# FaultRelay.net
KiCad netlist of a schematic drawn in Altium Designer
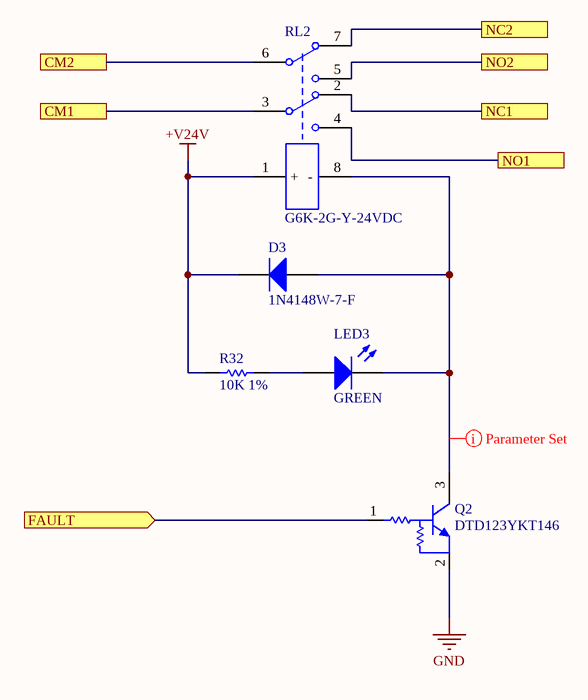
[diagram p0: FaultRelay.SchDoc]

(export (version "E")
  (design (tool "Eeschema 10.0.6"))
  (components
    (comp (ref "D3")
      (value "1N4148W-7-F")
      (footprint "MC1:DIOD-SOD123-2_V")
      (description "DIODE GEN PURP 100V 300MA SOD123")
      (fields (field (name "MANUFACTURER") "Diodes") (field (name "VOLTAGE") "100V"))
      (libsource (lib "MC1") (part "1N4148W-7-F"))
    )
    (comp (ref "LED3")
      (value "GREEN")
      (footprint "LED0805")
      (description "LED GREEN CLEAR 0805 SMD")
      (fields
        (field (name "MANUFACTURER") "Wurth Electronics")
        (field (name "MANUFACTURER PART NUMBER") "150080VS75000")
      )
      (libsource (lib "MCx") (part "150080VS75000"))
    )
    (comp (ref "Q2")
      (value "DTD123YKT146")
      (footprint "MC1:SOT95P280X130-3N")
      (description "TRANS PREBIAS NPN 200MW SMT3")
      (fields (field (name "MANUFACTURER") "Rohm"))
      (libsource (lib "MC1") (part "DTD123YKT146"))
    )
    (comp (ref "R32")
      (value "10K 1%")
      (footprint "R0805")
      (fields
        (field (name "MANUFACTURER") "Vishay")
        (field (name "MANUFACTURER PART NUMBER") "CRCW080510K0FKEA")
        (field (name "TOLERANCE") "1%")
      )
      (libsource (lib "MCx") (part "CRCW080510K0FKEA"))
    )
    (comp (ref "RL2")
      (value "G6K-2G-Y-24VDC")
      (footprint "MC1:G6K-2F-Y")
      (description "Electromechanical Relay DPDT 1A 24VDC 5.22KOhm Surface Mount")
      (fields (field (name "MANUFACTURER") "Omron") (field (name "MANUFACTURER PART NUMBER") "G6K-2F-YDC24"))
      (libsource (lib "MC1") (part "G6K-2G-Y-24VDC"))
    )
  )
  (nets
    (net (code "1") (name "+V24V") (class "Default")
      (node (ref "D3") (pin "2") (pinfunction "K_2") (pintype "passive"))
      (node (ref "R32") (pin "1") (pinfunction "1_1") (pintype "passive"))
      (node (ref "RL2") (pin "1") (pinfunction "+_1") (pintype "passive"))
    )
    (net (code "2") (name "/CM1") (class "Default")
      (node (ref "RL2") (pin "3") (pinfunction "3_3") (pintype "passive"))
    )
    (net (code "3") (name "/CM2") (class "Default")
      (node (ref "RL2") (pin "6") (pinfunction "6_6") (pintype "passive"))
    )
    (net (code "4") (name "/FAULT") (class "Default")
      (node (ref "Q2") (pin "1") (pinfunction "B_1") (pintype "passive"))
    )
    (net (code "5") (name "/NC1") (class "Default")
      (node (ref "RL2") (pin "2") (pinfunction "2_2") (pintype "passive"))
    )
    (net (code "6") (name "/NC2") (class "Default")
      (node (ref "RL2") (pin "7") (pinfunction "7_7") (pintype "passive"))
    )
    (net (code "7") (name "/NO1") (class "Default")
      (node (ref "RL2") (pin "4") (pinfunction "4_4") (pintype "passive"))
    )
    (net (code "8") (name "/NO2") (class "Default")
      (node (ref "RL2") (pin "5") (pinfunction "5_5") (pintype "passive"))
    )
    (net (code "9") (name "GND") (class "Default")
      (node (ref "Q2") (pin "2") (pinfunction "E_2") (pintype "passive"))
    )
    (net (code "10") (name "Net-(D3-A)") (class "Default")
      (node (ref "D3") (pin "1") (pinfunction "A_1") (pintype "passive"))
      (node (ref "LED3") (pin "1") (pinfunction "K_1") (pintype "passive"))
      (node (ref "Q2") (pin "3") (pinfunction "C_3") (pintype "passive"))
      (node (ref "RL2") (pin "8") (pinfunction "-_8") (pintype "passive"))
    )
    (net (code "11") (name "Net-(LED3-A)") (class "Default")
      (node (ref "LED3") (pin "2") (pinfunction "A_2") (pintype "passive"))
      (node (ref "R32") (pin "2") (pinfunction "2_2") (pintype "passive"))
    )
  )
)
